# M896X.net
KiCad netlist of a schematic drawn in EAGLE
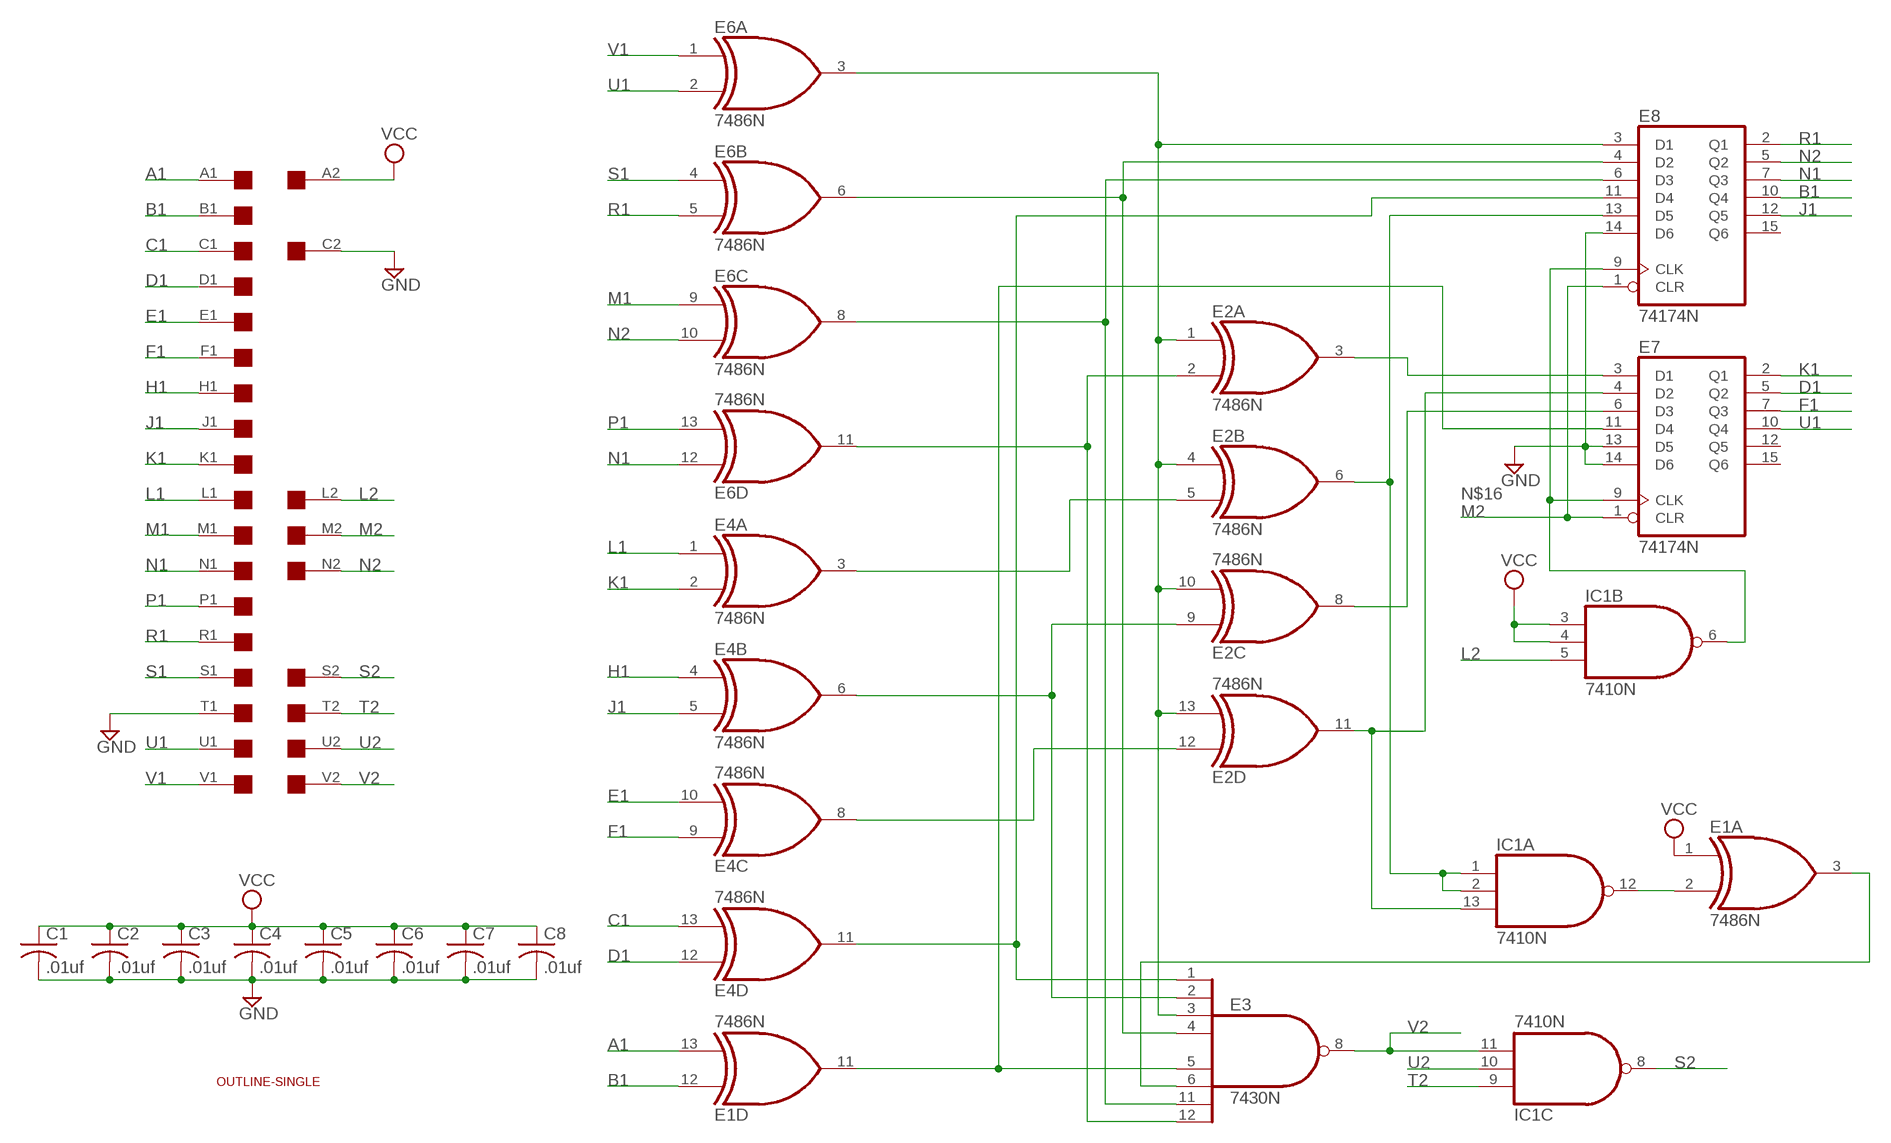
[diagram p0: schematic, sheet 1]

(export (version "E")
  (design (tool "Eeschema 10.0.6"))
  (components
    (comp (ref "C1")
      (value ".01uf")
      (footprint "eagle-import:C050-025X075")
      (libsource (lib "eagle-import") (part "C-US050-025X075"))
    )
    (comp (ref "C2")
      (value ".01uf")
      (footprint "eagle-import:C050-025X075")
      (libsource (lib "eagle-import") (part "C-US050-025X075"))
    )
    (comp (ref "C3")
      (value ".01uf")
      (footprint "eagle-import:C050-025X075")
      (libsource (lib "eagle-import") (part "C-US050-025X075"))
    )
    (comp (ref "C4")
      (value ".01uf")
      (footprint "eagle-import:C050-025X075")
      (libsource (lib "eagle-import") (part "C-US050-025X075"))
    )
    (comp (ref "C5")
      (value ".01uf")
      (footprint "eagle-import:C050-025X075")
      (libsource (lib "eagle-import") (part "C-US050-025X075"))
    )
    (comp (ref "C6")
      (value ".01uf")
      (footprint "eagle-import:C050-025X075")
      (libsource (lib "eagle-import") (part "C-US050-025X075"))
    )
    (comp (ref "C7")
      (value ".01uf")
      (footprint "eagle-import:C050-025X075")
      (libsource (lib "eagle-import") (part "C-US050-025X075"))
    )
    (comp (ref "C8")
      (value ".01uf")
      (footprint "eagle-import:C050-025X075")
      (libsource (lib "eagle-import") (part "C-US050-025X075"))
    )
    (comp (ref "E1")
      (value "7486N")
      (footprint "eagle-import:DIL14")
      (libsource (lib "eagle-import") (part "7486N"))
    )
    (comp (ref "E2")
      (value "7486N")
      (footprint "eagle-import:DIL14")
      (libsource (lib "eagle-import") (part "7486N"))
    )
    (comp (ref "E3")
      (value "7430N")
      (footprint "eagle-import:DIL14")
      (libsource (lib "eagle-import") (part "7430N"))
    )
    (comp (ref "E4")
      (value "7486N")
      (footprint "eagle-import:DIL14")
      (libsource (lib "eagle-import") (part "7486N"))
    )
    (comp (ref "E6")
      (value "7486N")
      (footprint "eagle-import:DIL14")
      (libsource (lib "eagle-import") (part "7486N"))
    )
    (comp (ref "E7")
      (value "74174N")
      (footprint "eagle-import:DIL16")
      (libsource (lib "eagle-import") (part "74174N"))
    )
    (comp (ref "E8")
      (value "74174N")
      (footprint "eagle-import:DIL16")
      (libsource (lib "eagle-import") (part "74174N"))
    )
    (comp (ref "IC1")
      (value "7410N")
      (footprint "eagle-import:DIL14")
      (libsource (lib "eagle-import") (part "7410N"))
    )
    (comp (ref "U$1")
      (value "EDGE-2CONNECTOR")
      (footprint "eagle-import:EDGE-CON2")
      (libsource (lib "eagle-import") (part "EDGE-2CONNECTOR"))
    )
    (comp (ref "U$4")
      (value "OUTLINE-SINGLE")
      (footprint "eagle-import:SINGLE")
      (libsource (lib "eagle-import") (part "OUTLINE-SINGLE"))
    )
  )
  (nets
    (net (code "1") (name "/A1") (class "Default")
      (node (ref "E1") (pin "13") (pinfunction "I1_13") (pintype "input"))
      (node (ref "U$1") (pin "A1") (pinfunction "1_A1") (pintype "bidirectional"))
    )
    (net (code "2") (name "/B1") (class "Default")
      (node (ref "E1") (pin "12") (pinfunction "I0_12") (pintype "input"))
      (node (ref "E8") (pin "10") (pinfunction "Q4_10") (pintype "output"))
      (node (ref "U$1") (pin "B1") (pinfunction "1_B1") (pintype "bidirectional"))
    )
    (net (code "3") (name "/C1") (class "Default")
      (node (ref "E4") (pin "13") (pinfunction "I1_13") (pintype "input"))
      (node (ref "U$1") (pin "C1") (pinfunction "1_C1") (pintype "bidirectional"))
    )
    (net (code "4") (name "/D1") (class "Default")
      (node (ref "E4") (pin "12") (pinfunction "I0_12") (pintype "input"))
      (node (ref "E7") (pin "5") (pinfunction "Q2_5") (pintype "output"))
      (node (ref "U$1") (pin "D1") (pinfunction "1_D1") (pintype "bidirectional"))
    )
    (net (code "5") (name "/E1") (class "Default")
      (node (ref "E4") (pin "10") (pinfunction "I1_10") (pintype "input"))
      (node (ref "U$1") (pin "E1") (pinfunction "1_E1") (pintype "bidirectional"))
    )
    (net (code "6") (name "/F1") (class "Default")
      (node (ref "E4") (pin "9") (pinfunction "I0_9") (pintype "input"))
      (node (ref "E7") (pin "7") (pinfunction "Q3_7") (pintype "output"))
      (node (ref "U$1") (pin "F1") (pinfunction "1_F1") (pintype "bidirectional"))
    )
    (net (code "7") (name "/H1") (class "Default")
      (node (ref "E4") (pin "4") (pinfunction "I0_4") (pintype "input"))
      (node (ref "U$1") (pin "H1") (pinfunction "1_H1") (pintype "bidirectional"))
    )
    (net (code "8") (name "/J1") (class "Default")
      (node (ref "E4") (pin "5") (pinfunction "I1_5") (pintype "input"))
      (node (ref "E8") (pin "12") (pinfunction "Q5_12") (pintype "output"))
      (node (ref "U$1") (pin "J1") (pinfunction "1_J1") (pintype "bidirectional"))
    )
    (net (code "9") (name "/K1") (class "Default")
      (node (ref "E4") (pin "2") (pinfunction "I1_2") (pintype "input"))
      (node (ref "E7") (pin "2") (pinfunction "Q1_2") (pintype "output"))
      (node (ref "U$1") (pin "K1") (pinfunction "1_K1") (pintype "bidirectional"))
    )
    (net (code "10") (name "/L1") (class "Default")
      (node (ref "E4") (pin "1") (pinfunction "I0_1") (pintype "input"))
      (node (ref "U$1") (pin "L1") (pinfunction "1_L1") (pintype "bidirectional"))
    )
    (net (code "11") (name "/L2") (class "Default")
      (node (ref "IC1") (pin "5") (pinfunction "I2_5") (pintype "input"))
      (node (ref "U$1") (pin "L2") (pinfunction "1_L2") (pintype "bidirectional"))
    )
    (net (code "12") (name "/M1") (class "Default")
      (node (ref "E6") (pin "9") (pinfunction "I0_9") (pintype "input"))
      (node (ref "U$1") (pin "M1") (pinfunction "1_M1") (pintype "bidirectional"))
    )
    (net (code "13") (name "/M2") (class "Default")
      (node (ref "E7") (pin "1") (pinfunction "CLR_1") (pintype "input"))
      (node (ref "E8") (pin "1") (pinfunction "CLR_1") (pintype "input"))
      (node (ref "U$1") (pin "M2") (pinfunction "1_M2") (pintype "bidirectional"))
    )
    (net (code "14") (name "/N$16") (class "Default")
      (node (ref "E7") (pin "9") (pinfunction "CLK_9") (pintype "input"))
      (node (ref "E8") (pin "9") (pinfunction "CLK_9") (pintype "input"))
      (node (ref "IC1") (pin "6") (pinfunction "O_6") (pintype "output"))
    )
    (net (code "15") (name "/N1") (class "Default")
      (node (ref "E6") (pin "12") (pinfunction "I0_12") (pintype "input"))
      (node (ref "E8") (pin "7") (pinfunction "Q3_7") (pintype "output"))
      (node (ref "U$1") (pin "N1") (pinfunction "1_N1") (pintype "bidirectional"))
    )
    (net (code "16") (name "/N2") (class "Default")
      (node (ref "E6") (pin "10") (pinfunction "I1_10") (pintype "input"))
      (node (ref "E8") (pin "5") (pinfunction "Q2_5") (pintype "output"))
      (node (ref "U$1") (pin "N2") (pinfunction "1_N2") (pintype "bidirectional"))
    )
    (net (code "17") (name "/P1") (class "Default")
      (node (ref "E6") (pin "13") (pinfunction "I1_13") (pintype "input"))
      (node (ref "U$1") (pin "P1") (pinfunction "1_P1") (pintype "bidirectional"))
    )
    (net (code "18") (name "/R1") (class "Default")
      (node (ref "E6") (pin "5") (pinfunction "I1_5") (pintype "input"))
      (node (ref "E8") (pin "2") (pinfunction "Q1_2") (pintype "output"))
      (node (ref "U$1") (pin "R1") (pinfunction "1_R1") (pintype "bidirectional"))
    )
    (net (code "19") (name "/S1") (class "Default")
      (node (ref "E6") (pin "4") (pinfunction "I0_4") (pintype "input"))
      (node (ref "U$1") (pin "S1") (pinfunction "1_S1") (pintype "bidirectional"))
    )
    (net (code "20") (name "/S2") (class "Default")
      (node (ref "IC1") (pin "8") (pinfunction "O_8") (pintype "output"))
      (node (ref "U$1") (pin "S2") (pinfunction "1_S2") (pintype "bidirectional"))
    )
    (net (code "21") (name "/T2") (class "Default")
      (node (ref "IC1") (pin "9") (pinfunction "I0_9") (pintype "input"))
      (node (ref "U$1") (pin "T2") (pinfunction "1_T2") (pintype "bidirectional"))
    )
    (net (code "22") (name "/U1") (class "Default")
      (node (ref "E6") (pin "2") (pinfunction "I1_2") (pintype "input"))
      (node (ref "E7") (pin "10") (pinfunction "Q4_10") (pintype "output"))
      (node (ref "U$1") (pin "U1") (pinfunction "1_U1") (pintype "bidirectional"))
    )
    (net (code "23") (name "/U2") (class "Default")
      (node (ref "IC1") (pin "10") (pinfunction "I1_10") (pintype "input"))
      (node (ref "U$1") (pin "U2") (pinfunction "1_U2") (pintype "bidirectional"))
    )
    (net (code "24") (name "/V1") (class "Default")
      (node (ref "E6") (pin "1") (pinfunction "I0_1") (pintype "input"))
      (node (ref "U$1") (pin "V1") (pinfunction "1_V1") (pintype "bidirectional"))
    )
    (net (code "25") (name "/V2") (class "Default")
      (node (ref "E3") (pin "8") (pinfunction "O_8") (pintype "output"))
      (node (ref "IC1") (pin "11") (pinfunction "I2_11") (pintype "input"))
      (node (ref "U$1") (pin "V2") (pinfunction "1_V2") (pintype "bidirectional"))
    )
    (net (code "26") (name "GND") (class "Default")
      (node (ref "C1") (pin "2") (pinfunction "2_2") (pintype "passive"))
      (node (ref "C2") (pin "2") (pinfunction "2_2") (pintype "passive"))
      (node (ref "C3") (pin "2") (pinfunction "2_2") (pintype "passive"))
      (node (ref "C4") (pin "2") (pinfunction "2_2") (pintype "passive"))
      (node (ref "C5") (pin "2") (pinfunction "2_2") (pintype "passive"))
      (node (ref "C6") (pin "2") (pinfunction "2_2") (pintype "passive"))
      (node (ref "C7") (pin "2") (pinfunction "2_2") (pintype "passive"))
      (node (ref "C8") (pin "2") (pinfunction "2_2") (pintype "passive"))
      (node (ref "E7") (pin "13") (pinfunction "D5_13") (pintype "input"))
      (node (ref "E7") (pin "14") (pinfunction "D6_14") (pintype "input"))
      (node (ref "E8") (pin "14") (pinfunction "D6_14") (pintype "input"))
      (node (ref "U$1") (pin "C2") (pinfunction "1_C2") (pintype "bidirectional"))
      (node (ref "U$1") (pin "T1") (pinfunction "1_T1") (pintype "bidirectional"))
    )
    (net (code "27") (name "Net-(E1A-I1)") (class "Default")
      (node (ref "E1") (pin "2") (pinfunction "I1_2") (pintype "input"))
      (node (ref "IC1") (pin "12") (pinfunction "O_12") (pintype "output"))
    )
    (net (code "28") (name "Net-(E1A-O)") (class "Default")
      (node (ref "E1") (pin "3") (pinfunction "O_3") (pintype "output"))
      (node (ref "E3") (pin "6") (pinfunction "I5_6") (pintype "input"))
    )
    (net (code "29") (name "Net-(E1D-O)") (class "Default")
      (node (ref "E1") (pin "11") (pinfunction "O_11") (pintype "output"))
      (node (ref "E3") (pin "5") (pinfunction "I4_5") (pintype "input"))
      (node (ref "E7") (pin "11") (pinfunction "D4_11") (pintype "input"))
    )
    (net (code "30") (name "Net-(E2A-I0)") (class "Default")
      (node (ref "E2") (pin "1") (pinfunction "I0_1") (pintype "input"))
      (node (ref "E2") (pin "10") (pinfunction "I1_10") (pintype "input"))
      (node (ref "E2") (pin "13") (pinfunction "I1_13") (pintype "input"))
      (node (ref "E2") (pin "4") (pinfunction "I0_4") (pintype "input"))
      (node (ref "E3") (pin "3") (pinfunction "I2_3") (pintype "input"))
      (node (ref "E6") (pin "3") (pinfunction "O_3") (pintype "output"))
      (node (ref "E8") (pin "3") (pinfunction "D1_3") (pintype "input"))
    )
    (net (code "31") (name "Net-(E2A-I1)") (class "Default")
      (node (ref "E2") (pin "2") (pinfunction "I1_2") (pintype "input"))
      (node (ref "E3") (pin "12") (pinfunction "I7_12") (pintype "input"))
      (node (ref "E6") (pin "11") (pinfunction "O_11") (pintype "output"))
    )
    (net (code "32") (name "Net-(E2A-O)") (class "Default")
      (node (ref "E2") (pin "3") (pinfunction "O_3") (pintype "output"))
      (node (ref "E7") (pin "3") (pinfunction "D1_3") (pintype "input"))
    )
    (net (code "33") (name "Net-(E2B-I1)") (class "Default")
      (node (ref "E2") (pin "5") (pinfunction "I1_5") (pintype "input"))
      (node (ref "E4") (pin "3") (pinfunction "O_3") (pintype "output"))
    )
    (net (code "34") (name "Net-(E2B-O)") (class "Default")
      (node (ref "E2") (pin "6") (pinfunction "O_6") (pintype "output"))
      (node (ref "E8") (pin "13") (pinfunction "D5_13") (pintype "input"))
      (node (ref "IC1") (pin "1") (pinfunction "I0_1") (pintype "input"))
      (node (ref "IC1") (pin "2") (pinfunction "I1_2") (pintype "input"))
    )
    (net (code "35") (name "Net-(E2C-I0)") (class "Default")
      (node (ref "E2") (pin "9") (pinfunction "I0_9") (pintype "input"))
      (node (ref "E3") (pin "2") (pinfunction "I1_2") (pintype "input"))
      (node (ref "E4") (pin "6") (pinfunction "O_6") (pintype "output"))
    )
    (net (code "36") (name "Net-(E2C-O)") (class "Default")
      (node (ref "E2") (pin "8") (pinfunction "O_8") (pintype "output"))
      (node (ref "E7") (pin "6") (pinfunction "D3_6") (pintype "input"))
    )
    (net (code "37") (name "Net-(E2D-I0)") (class "Default")
      (node (ref "E2") (pin "12") (pinfunction "I0_12") (pintype "input"))
      (node (ref "E4") (pin "8") (pinfunction "O_8") (pintype "output"))
    )
    (net (code "38") (name "Net-(E2D-O)") (class "Default")
      (node (ref "E2") (pin "11") (pinfunction "O_11") (pintype "output"))
      (node (ref "E7") (pin "4") (pinfunction "D2_4") (pintype "input"))
      (node (ref "IC1") (pin "13") (pinfunction "I2_13") (pintype "input"))
    )
    (net (code "39") (name "Net-(E3A-I0)") (class "Default")
      (node (ref "E3") (pin "1") (pinfunction "I0_1") (pintype "input"))
      (node (ref "E4") (pin "11") (pinfunction "O_11") (pintype "output"))
      (node (ref "E8") (pin "11") (pinfunction "D4_11") (pintype "input"))
    )
    (net (code "40") (name "Net-(E3A-I3)") (class "Default")
      (node (ref "E3") (pin "4") (pinfunction "I3_4") (pintype "input"))
      (node (ref "E6") (pin "6") (pinfunction "O_6") (pintype "output"))
      (node (ref "E8") (pin "4") (pinfunction "D2_4") (pintype "input"))
    )
    (net (code "41") (name "Net-(E3A-I6)") (class "Default")
      (node (ref "E3") (pin "11") (pinfunction "I6_11") (pintype "input"))
      (node (ref "E6") (pin "8") (pinfunction "O_8") (pintype "output"))
      (node (ref "E8") (pin "6") (pinfunction "D3_6") (pintype "input"))
    )
    (net (code "42") (name "VCC") (class "Default")
      (node (ref "C1") (pin "1") (pinfunction "1_1") (pintype "passive"))
      (node (ref "C2") (pin "1") (pinfunction "1_1") (pintype "passive"))
      (node (ref "C3") (pin "1") (pinfunction "1_1") (pintype "passive"))
      (node (ref "C4") (pin "1") (pinfunction "1_1") (pintype "passive"))
      (node (ref "C5") (pin "1") (pinfunction "1_1") (pintype "passive"))
      (node (ref "C6") (pin "1") (pinfunction "1_1") (pintype "passive"))
      (node (ref "C7") (pin "1") (pinfunction "1_1") (pintype "passive"))
      (node (ref "C8") (pin "1") (pinfunction "1_1") (pintype "passive"))
      (node (ref "E1") (pin "1") (pinfunction "I0_1") (pintype "input"))
      (node (ref "IC1") (pin "3") (pinfunction "I0_3") (pintype "input"))
      (node (ref "IC1") (pin "4") (pinfunction "I1_4") (pintype "input"))
      (node (ref "U$1") (pin "A2") (pinfunction "1_A2") (pintype "bidirectional"))
    )
    (net (code "43") (name "unconnected-(E7A-Q5-Pad12)") (class "Default")
      (node (ref "E7") (pin "12") (pinfunction "Q5_12") (pintype "output"))
    )
    (net (code "44") (name "unconnected-(E7A-Q6-Pad15)") (class "Default")
      (node (ref "E7") (pin "15") (pinfunction "Q6_15") (pintype "output"))
    )
    (net (code "45") (name "unconnected-(E8A-Q6-Pad15)") (class "Default")
      (node (ref "E8") (pin "15") (pinfunction "Q6_15") (pintype "output"))
    )
  )
)
